# ESP32_backup.net
KiCad netlist of a schematic drawn in Altium Designer
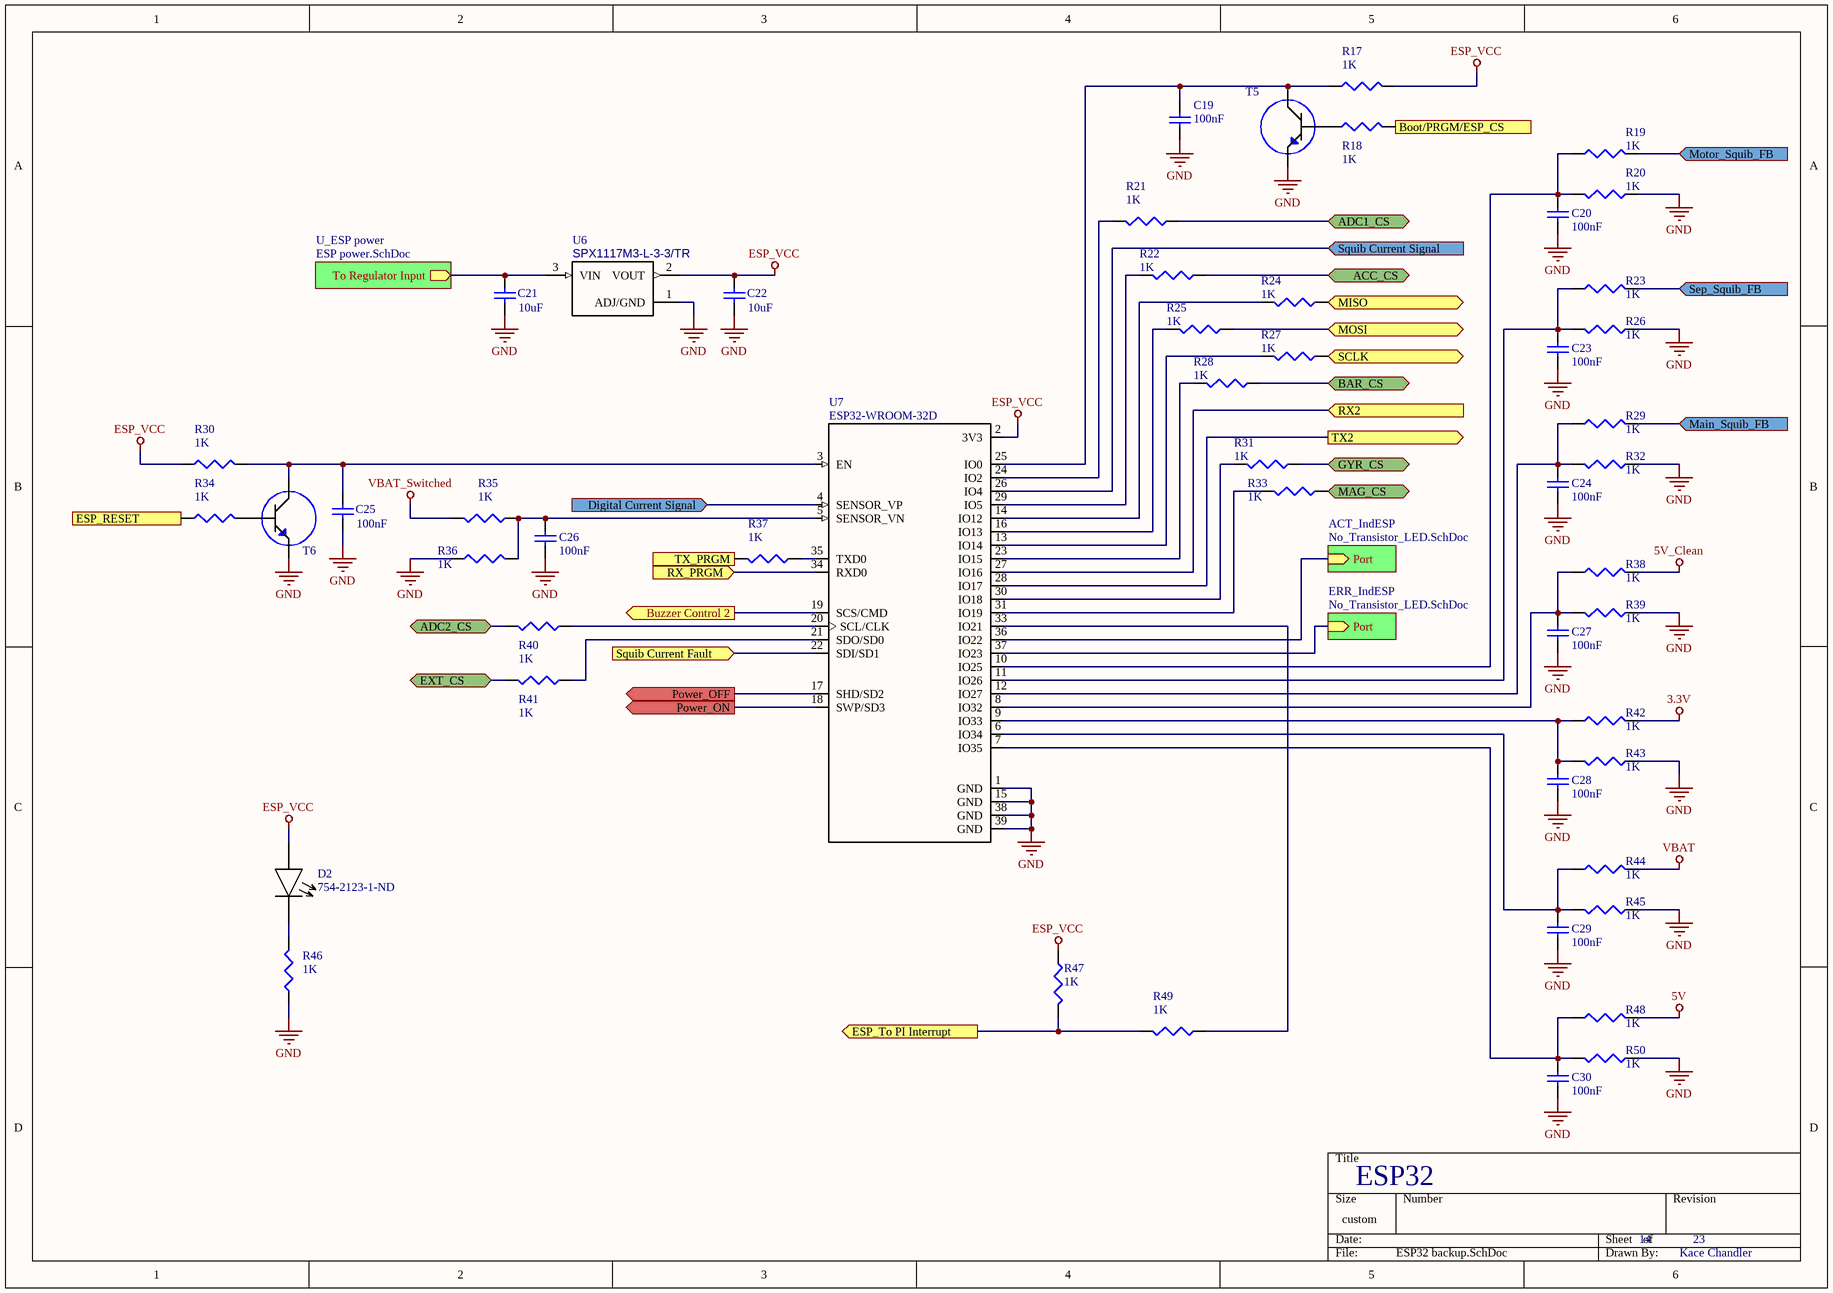
[diagram p0: ESP32 backup.SchDoc]

(export (version "E")
  (design (tool "Eeschema 10.0.6"))
  (components
    (comp (ref "C19")
      (value "100nF")
      (footprint "0805 Footprint")
      (fields (field (name "Comment") "Cap"))
      (libsource (lib "RC0805FR-0751K1L") (part "Cap"))
    )
    (comp (ref "C20")
      (value "100nF")
      (footprint "0603 Footprint")
      (description "Capacitor")
      (fields (field (name "Comment") "Cap") (field (name "PUBLISHER") "Altium Limited"))
      (libsource (lib "Miscellaneous Devices") (part "Cap"))
    )
    (comp (ref "C21")
      (value "10uF")
      (footprint "0805 Footprint")
      (description "Capacitor")
      (fields (field (name "Comment") "Cap") (field (name "PUBLISHER") "Altium Limited"))
      (libsource (lib "Miscellaneous Devices") (part "Cap"))
    )
    (comp (ref "C22")
      (value "10uF")
      (footprint "0805 Footprint")
      (description "Capacitor")
      (fields (field (name "Comment") "Cap") (field (name "PUBLISHER") "Altium Limited"))
      (libsource (lib "Miscellaneous Devices") (part "Cap"))
    )
    (comp (ref "C23")
      (value "100nF")
      (footprint "0603 Footprint")
      (description "Capacitor")
      (fields (field (name "Comment") "Cap") (field (name "PUBLISHER") "Altium Limited"))
      (libsource (lib "Miscellaneous Devices") (part "Cap"))
    )
    (comp (ref "C24")
      (value "100nF")
      (footprint "0603 Footprint")
      (description "Capacitor")
      (fields (field (name "Comment") "Cap") (field (name "PUBLISHER") "Altium Limited"))
      (libsource (lib "Miscellaneous Devices") (part "Cap"))
    )
    (comp (ref "C25")
      (value "100nF")
      (footprint "0805 Footprint")
      (fields (field (name "Comment") "Cap"))
      (libsource (lib "RC0805FR-0751K1L") (part "Cap"))
    )
    (comp (ref "C26")
      (value "100nF")
      (footprint "0603 Footprint")
      (description "Capacitor")
      (fields (field (name "Comment") "Cap") (field (name "PUBLISHER") "Altium Limited"))
      (libsource (lib "Miscellaneous Devices") (part "Cap"))
    )
    (comp (ref "C27")
      (value "100nF")
      (footprint "0603 Footprint")
      (description "Capacitor")
      (fields (field (name "Comment") "Cap") (field (name "PUBLISHER") "Altium Limited"))
      (libsource (lib "Miscellaneous Devices") (part "Cap"))
    )
    (comp (ref "C28")
      (value "100nF")
      (footprint "0603 Footprint")
      (description "Capacitor")
      (fields (field (name "Comment") "Cap") (field (name "PUBLISHER") "Altium Limited"))
      (libsource (lib "Miscellaneous Devices") (part "Cap"))
    )
    (comp (ref "C29")
      (value "100nF")
      (footprint "0603 Footprint")
      (description "Capacitor")
      (fields (field (name "Comment") "Cap") (field (name "PUBLISHER") "Altium Limited"))
      (libsource (lib "Miscellaneous Devices") (part "Cap"))
    )
    (comp (ref "C30")
      (value "100nF")
      (footprint "0603 Footprint")
      (description "Capacitor")
      (fields (field (name "Comment") "Cap") (field (name "PUBLISHER") "Altium Limited"))
      (libsource (lib "Miscellaneous Devices") (part "Cap"))
    )
    (comp (ref "D2")
      (value "LED_R")
      (footprint "0402 footprint")
      (fields (field (name "SUPPLIER PART NUMBER 1") "754-2123-1-ND"))
      (libsource (lib "AvionicsParts") (part "LED_R"))
    )
    (comp (ref "R17")
      (value "1K")
      (description "Resistor")
      (fields (field (name "Comment") "Res3") (field (name "PUBLISHER") "Altium Limited"))
      (libsource (lib "Miscellaneous Devices") (part "Res3"))
    )
    (comp (ref "R18")
      (value "1K")
      (description "Resistor")
      (fields (field (name "Comment") "Res3") (field (name "PUBLISHER") "Altium Limited"))
      (libsource (lib "Miscellaneous Devices") (part "Res3"))
    )
    (comp (ref "R19")
      (value "1K")
      (description "Resistor")
      (fields (field (name "Comment") "Res3") (field (name "PUBLISHER") "Altium Limited"))
      (libsource (lib "Miscellaneous Devices") (part "Res3"))
    )
    (comp (ref "R20")
      (value "1K")
      (description "Resistor")
      (fields (field (name "Comment") "Res3") (field (name "PUBLISHER") "Altium Limited"))
      (libsource (lib "Miscellaneous Devices") (part "Res3"))
    )
    (comp (ref "R21")
      (value "1K")
      (description "Resistor")
      (fields (field (name "Comment") "Res3") (field (name "PUBLISHER") "Altium Limited"))
      (libsource (lib "Miscellaneous Devices") (part "Res3"))
    )
    (comp (ref "R22")
      (value "1K")
      (description "Resistor")
      (fields (field (name "Comment") "Res3") (field (name "PUBLISHER") "Altium Limited"))
      (libsource (lib "Miscellaneous Devices") (part "Res3"))
    )
    (comp (ref "R23")
      (value "1K")
      (description "Resistor")
      (fields (field (name "Comment") "Res3") (field (name "PUBLISHER") "Altium Limited"))
      (libsource (lib "Miscellaneous Devices") (part "Res3"))
    )
    (comp (ref "R24")
      (value "1K")
      (description "Resistor")
      (fields (field (name "Comment") "Res3") (field (name "PUBLISHER") "Altium Limited"))
      (libsource (lib "Miscellaneous Devices") (part "Res3"))
    )
    (comp (ref "R25")
      (value "1K")
      (description "Resistor")
      (fields (field (name "Comment") "Res3") (field (name "PUBLISHER") "Altium Limited"))
      (libsource (lib "Miscellaneous Devices") (part "Res3"))
    )
    (comp (ref "R26")
      (value "1K")
      (description "Resistor")
      (fields (field (name "Comment") "Res3") (field (name "PUBLISHER") "Altium Limited"))
      (libsource (lib "Miscellaneous Devices") (part "Res3"))
    )
    (comp (ref "R27")
      (value "1K")
      (description "Resistor")
      (fields (field (name "Comment") "Res3") (field (name "PUBLISHER") "Altium Limited"))
      (libsource (lib "Miscellaneous Devices") (part "Res3"))
    )
    (comp (ref "R28")
      (value "1K")
      (description "Resistor")
      (fields (field (name "Comment") "Res3") (field (name "PUBLISHER") "Altium Limited"))
      (libsource (lib "Miscellaneous Devices") (part "Res3"))
    )
    (comp (ref "R29")
      (value "1K")
      (description "Resistor")
      (fields (field (name "Comment") "Res3") (field (name "PUBLISHER") "Altium Limited"))
      (libsource (lib "Miscellaneous Devices") (part "Res3"))
    )
    (comp (ref "R30")
      (value "1K")
      (description "Resistor")
      (fields (field (name "Comment") "Res3") (field (name "PUBLISHER") "Altium Limited"))
      (libsource (lib "Miscellaneous Devices") (part "Res3"))
    )
    (comp (ref "R31")
      (value "1K")
      (description "Resistor")
      (fields (field (name "Comment") "Res3") (field (name "PUBLISHER") "Altium Limited"))
      (libsource (lib "Miscellaneous Devices") (part "Res3"))
    )
    (comp (ref "R32")
      (value "1K")
      (description "Resistor")
      (fields (field (name "Comment") "Res3") (field (name "PUBLISHER") "Altium Limited"))
      (libsource (lib "Miscellaneous Devices") (part "Res3"))
    )
    (comp (ref "R33")
      (value "1K")
      (description "Resistor")
      (fields (field (name "Comment") "Res3") (field (name "PUBLISHER") "Altium Limited"))
      (libsource (lib "Miscellaneous Devices") (part "Res3"))
    )
    (comp (ref "R34")
      (value "1K")
      (description "Resistor")
      (fields (field (name "Comment") "Res3") (field (name "PUBLISHER") "Altium Limited"))
      (libsource (lib "Miscellaneous Devices") (part "Res3"))
    )
    (comp (ref "R35")
      (value "1K")
      (description "Resistor")
      (fields (field (name "Comment") "Res3") (field (name "PUBLISHER") "Altium Limited"))
      (libsource (lib "Miscellaneous Devices") (part "Res3"))
    )
    (comp (ref "R36")
      (value "1K")
      (description "Resistor")
      (fields (field (name "Comment") "Res3") (field (name "PUBLISHER") "Altium Limited"))
      (libsource (lib "Miscellaneous Devices") (part "Res3"))
    )
    (comp (ref "R37")
      (value "1K")
      (description "Resistor")
      (fields (field (name "Comment") "Res3") (field (name "PUBLISHER") "Altium Limited"))
      (libsource (lib "Miscellaneous Devices") (part "Res3"))
    )
    (comp (ref "R38")
      (value "1K")
      (description "Resistor")
      (fields (field (name "Comment") "Res3") (field (name "PUBLISHER") "Altium Limited"))
      (libsource (lib "Miscellaneous Devices") (part "Res3"))
    )
    (comp (ref "R39")
      (value "1K")
      (description "Resistor")
      (fields (field (name "Comment") "Res3") (field (name "PUBLISHER") "Altium Limited"))
      (libsource (lib "Miscellaneous Devices") (part "Res3"))
    )
    (comp (ref "R40")
      (value "1K")
      (description "Resistor")
      (fields (field (name "Comment") "Res3") (field (name "PUBLISHER") "Altium Limited"))
      (libsource (lib "Miscellaneous Devices") (part "Res3"))
    )
    (comp (ref "R41")
      (value "1K")
      (description "Resistor")
      (fields (field (name "Comment") "Res3") (field (name "PUBLISHER") "Altium Limited"))
      (libsource (lib "Miscellaneous Devices") (part "Res3"))
    )
    (comp (ref "R42")
      (value "1K")
      (description "Resistor")
      (fields (field (name "Comment") "Res3") (field (name "PUBLISHER") "Altium Limited"))
      (libsource (lib "Miscellaneous Devices") (part "Res3"))
    )
    (comp (ref "R43")
      (value "1K")
      (description "Resistor")
      (fields (field (name "Comment") "Res3") (field (name "PUBLISHER") "Altium Limited"))
      (libsource (lib "Miscellaneous Devices") (part "Res3"))
    )
    (comp (ref "R44")
      (value "1K")
      (description "Resistor")
      (fields (field (name "Comment") "Res3") (field (name "PUBLISHER") "Altium Limited"))
      (libsource (lib "Miscellaneous Devices") (part "Res3"))
    )
    (comp (ref "R45")
      (value "1K")
      (description "Resistor")
      (fields (field (name "Comment") "Res3") (field (name "PUBLISHER") "Altium Limited"))
      (libsource (lib "Miscellaneous Devices") (part "Res3"))
    )
    (comp (ref "R46")
      (value "1K")
      (description "Resistor")
      (fields (field (name "Comment") "Res3") (field (name "PUBLISHER") "Altium Limited"))
      (libsource (lib "Miscellaneous Devices") (part "Res3"))
    )
    (comp (ref "R47")
      (value "1K")
      (footprint "J1-0603")
      (description "Resistor")
      (fields (field (name "Comment") "Res3") (field (name "PUBLISHER") "Altium Limited"))
      (libsource (lib "Miscellaneous Devices") (part "Res3"))
    )
    (comp (ref "R48")
      (value "1K")
      (description "Resistor")
      (fields (field (name "Comment") "Res3") (field (name "PUBLISHER") "Altium Limited"))
      (libsource (lib "Miscellaneous Devices") (part "Res3"))
    )
    (comp (ref "R49")
      (value "1K")
      (description "Resistor")
      (fields (field (name "Comment") "Res3") (field (name "PUBLISHER") "Altium Limited"))
      (libsource (lib "Miscellaneous Devices") (part "Res3"))
    )
    (comp (ref "R50")
      (value "1K")
      (description "Resistor")
      (fields (field (name "Comment") "Res3") (field (name "PUBLISHER") "Altium Limited"))
      (libsource (lib "Miscellaneous Devices") (part "Res3"))
    )
    (comp (ref "T5")
      (value "MMBT2222ALT1")
      (footprint "BJT")
      (description "Trans NPN 40V 0.6A SOT23")
      (fields (field (name "MF") "ON Semiconductor"))
      (libsource (lib "AvionicsParts") (part "BJT NPN"))
    )
    (comp (ref "T6")
      (value "MMBT2222ALT1")
      (footprint "BJT")
      (description "Trans NPN 40V 0.6A SOT23")
      (fields (field (name "MF") "ON Semiconductor"))
      (libsource (lib "AvionicsParts") (part "BJT NPN"))
    )
    (comp (ref "U6")
      (value "3.3V Regulator")
      (footprint "*DPAK229P990X238-4N")
      (description "NCP1117DT33T5GOSCT-ND 3.3V linear regulator")
      (fields (field (name "MF") "MaxLinear, Inc.") (field (name "MP") "SPX1117M3-L-3-3/TR"))
      (libsource (lib "AvionicsParts") (part "3-3VReg"))
    )
    (comp (ref "U7")
      (value "ESP32-WROOM-32D")
      (footprint "*MODULE_ESP32-WROOM-32D")
      (description "IC: SoC; GPIO, I2C, I2S, IR, SD, SDIO, SPI, UART; 2.7Ã·3.6VDC; 20dBm")
      (fields (field (name "MF") "Espressif Systems"))
      (libsource (lib "AvionicsParts") (part "ESP32-WROOM-32D"))
    )
  )
  (nets
    (net (code "1") (name "/ACC_CS") (class "Default")
      (node (ref "R22") (pin "1") (pinfunction "1_1") (pintype "passive"))
    )
    (net (code "2") (name "/ADC1_CS") (class "Default")
      (node (ref "R21") (pin "1") (pinfunction "1_1") (pintype "passive"))
    )
    (net (code "3") (name "/ADC2_CS") (class "Default")
      (node (ref "R40") (pin "2") (pinfunction "2_2") (pintype "passive"))
    )
    (net (code "4") (name "/BAR_CS") (class "Default")
      (node (ref "R28") (pin "1") (pinfunction "1_1") (pintype "passive"))
    )
    (net (code "5") (name "/Boot{slash}PRGM{slash}ESP_CS") (class "Default")
      (node (ref "R18") (pin "2") (pinfunction "2_2") (pintype "passive"))
    )
    (net (code "6") (name "/Buzzer Control 2") (class "Default")
      (node (ref "U7") (pin "19") (pinfunction "SCS/CMD_19") (pintype "bidirectional"))
    )
    (net (code "7") (name "/Digital Current Signal") (class "Default")
      (node (ref "U7") (pin "4") (pinfunction "SENSOR_VP_4") (pintype "input"))
    )
    (net (code "8") (name "/ESP_RESET") (class "Default")
      (node (ref "R34") (pin "1") (pinfunction "1_1") (pintype "passive"))
    )
    (net (code "9") (name "/ESP_To PI Interrupt") (class "Default")
      (node (ref "R47") (pin "2") (pinfunction "2_2") (pintype "passive"))
      (node (ref "R49") (pin "2") (pinfunction "2_2") (pintype "passive"))
    )
    (net (code "10") (name "/EXT_CS") (class "Default")
      (node (ref "R41") (pin "2") (pinfunction "2_2") (pintype "passive"))
    )
    (net (code "11") (name "/GYR_CS") (class "Default")
      (node (ref "R31") (pin "1") (pinfunction "1_1") (pintype "passive"))
    )
    (net (code "12") (name "/MAG_CS") (class "Default")
      (node (ref "R33") (pin "1") (pinfunction "1_1") (pintype "passive"))
    )
    (net (code "13") (name "/MISO") (class "Default")
      (node (ref "R24") (pin "1") (pinfunction "1_1") (pintype "passive"))
    )
    (net (code "14") (name "/MOSI") (class "Default")
      (node (ref "R25") (pin "1") (pinfunction "1_1") (pintype "passive"))
    )
    (net (code "15") (name "/Main_Squib_FB") (class "Default")
      (node (ref "R29") (pin "2") (pinfunction "2_2") (pintype "passive"))
    )
    (net (code "16") (name "/Motor_Squib_FB") (class "Default")
      (node (ref "R19") (pin "2") (pinfunction "2_2") (pintype "passive"))
    )
    (net (code "17") (name "/Port") (class "Default")
      (node (ref "U7") (pin "37") (pinfunction "IO23_37") (pintype "bidirectional"))
    )
    (net (code "18") (name "/Port_1") (class "Default")
      (node (ref "U7") (pin "36") (pinfunction "IO22_36") (pintype "bidirectional"))
    )
    (net (code "19") (name "/Power_OFF") (class "Default")
      (node (ref "U7") (pin "17") (pinfunction "SHD/SD2_17") (pintype "bidirectional"))
    )
    (net (code "20") (name "/Power_ON") (class "Default")
      (node (ref "U7") (pin "18") (pinfunction "SWP/SD3_18") (pintype "bidirectional"))
    )
    (net (code "21") (name "/RX2") (class "Default")
      (node (ref "U7") (pin "27") (pinfunction "IO16_27") (pintype "bidirectional"))
    )
    (net (code "22") (name "/RX_PRGM") (class "Default")
      (node (ref "U7") (pin "34") (pinfunction "RXD0_34") (pintype "bidirectional"))
    )
    (net (code "23") (name "/SCLK") (class "Default")
      (node (ref "R27") (pin "1") (pinfunction "1_1") (pintype "passive"))
    )
    (net (code "24") (name "/Sep_Squib_FB") (class "Default")
      (node (ref "R23") (pin "2") (pinfunction "2_2") (pintype "passive"))
    )
    (net (code "25") (name "/Squib Current Fault") (class "Default")
      (node (ref "U7") (pin "22") (pinfunction "SDI/SD1_22") (pintype "bidirectional"))
    )
    (net (code "26") (name "/Squib Current Signal") (class "Default")
      (node (ref "U7") (pin "26") (pinfunction "IO4_26") (pintype "bidirectional"))
    )
    (net (code "27") (name "/TX2") (class "Default")
      (node (ref "U7") (pin "28") (pinfunction "IO17_28") (pintype "bidirectional"))
    )
    (net (code "28") (name "/TX_PRGM") (class "Default")
      (node (ref "R37") (pin "2") (pinfunction "2_2") (pintype "passive"))
    )
    (net (code "29") (name "/To Regulator Input") (class "Default")
      (node (ref "C21") (pin "2") (pinfunction "2_2") (pintype "passive"))
      (node (ref "U6") (pin "3") (pinfunction "VIN_3") (pintype "input"))
    )
    (net (code "30") (name "3.3V") (class "Default")
      (node (ref "R42") (pin "2") (pinfunction "2_2") (pintype "passive"))
    )
    (net (code "31") (name "5V") (class "Default")
      (node (ref "R48") (pin "2") (pinfunction "2_2") (pintype "passive"))
    )
    (net (code "32") (name "5V_Clean") (class "Default")
      (node (ref "R38") (pin "2") (pinfunction "2_2") (pintype "passive"))
    )
    (net (code "33") (name "ESP_VCC") (class "Default")
      (node (ref "C22") (pin "2") (pinfunction "2_2") (pintype "passive"))
      (node (ref "D2") (pin "1") (pinfunction "1_1") (pintype "passive"))
      (node (ref "R17") (pin "1") (pinfunction "1_1") (pintype "passive"))
      (node (ref "R30") (pin "1") (pinfunction "1_1") (pintype "passive"))
      (node (ref "R47") (pin "1") (pinfunction "1_1") (pintype "passive"))
      (node (ref "U6") (pin "2") (pinfunction "VOUT_2") (pintype "output"))
      (node (ref "U7") (pin "2") (pinfunction "3V3_2") (pintype "power_in"))
    )
    (net (code "34") (name "GND") (class "Default")
      (node (ref "C19") (pin "1") (pinfunction "1_1") (pintype "passive"))
      (node (ref "C20") (pin "1") (pinfunction "1_1") (pintype "passive"))
      (node (ref "C21") (pin "1") (pinfunction "1_1") (pintype "passive"))
      (node (ref "C22") (pin "1") (pinfunction "1_1") (pintype "passive"))
      (node (ref "C23") (pin "1") (pinfunction "1_1") (pintype "passive"))
      (node (ref "C24") (pin "1") (pinfunction "1_1") (pintype "passive"))
      (node (ref "C25") (pin "1") (pinfunction "1_1") (pintype "passive"))
      (node (ref "C26") (pin "1") (pinfunction "1_1") (pintype "passive"))
      (node (ref "C27") (pin "1") (pinfunction "1_1") (pintype "passive"))
      (node (ref "C28") (pin "1") (pinfunction "1_1") (pintype "passive"))
      (node (ref "C29") (pin "1") (pinfunction "1_1") (pintype "passive"))
      (node (ref "C30") (pin "1") (pinfunction "1_1") (pintype "passive"))
      (node (ref "R20") (pin "1") (pinfunction "1_1") (pintype "passive"))
      (node (ref "R26") (pin "1") (pinfunction "1_1") (pintype "passive"))
      (node (ref "R32") (pin "1") (pinfunction "1_1") (pintype "passive"))
      (node (ref "R36") (pin "1") (pinfunction "1_1") (pintype "passive"))
      (node (ref "R39") (pin "1") (pinfunction "1_1") (pintype "passive"))
      (node (ref "R43") (pin "1") (pinfunction "1_1") (pintype "passive"))
      (node (ref "R45") (pin "1") (pinfunction "1_1") (pintype "passive"))
      (node (ref "R46") (pin "1") (pinfunction "1_1") (pintype "passive"))
      (node (ref "R50") (pin "1") (pinfunction "1_1") (pintype "passive"))
      (node (ref "T5") (pin "2") (pinfunction "E_2") (pintype "passive"))
      (node (ref "T6") (pin "2") (pinfunction "E_2") (pintype "passive"))
      (node (ref "U6") (pin "1") (pinfunction "ADJ/GND_1") (pintype "power_in"))
      (node (ref "U7") (pin "1") (pinfunction "GND_1") (pintype "power_in"))
      (node (ref "U7") (pin "15") (pinfunction "GND_15") (pintype "power_in"))
      (node (ref "U7") (pin "38") (pinfunction "GND_38") (pintype "power_in"))
      (node (ref "U7") (pin "39") (pinfunction "GND_39") (pintype "power_in"))
    )
    (net (code "35") (name "Net-(D2-Pad2)") (class "Default")
      (node (ref "D2") (pin "2") (pinfunction "2_2") (pintype "passive"))
      (node (ref "R46") (pin "2") (pinfunction "2_2") (pintype "passive"))
    )
    (net (code "36") (name "Net-(T5-B)") (class "Default")
      (node (ref "R18") (pin "1") (pinfunction "1_1") (pintype "passive"))
      (node (ref "T5") (pin "1") (pinfunction "B_1") (pintype "passive"))
    )
    (net (code "37") (name "Net-(T5-C)") (class "Default")
      (node (ref "C19") (pin "2") (pinfunction "2_2") (pintype "passive"))
      (node (ref "R17") (pin "2") (pinfunction "2_2") (pintype "passive"))
      (node (ref "T5") (pin "3") (pinfunction "C_3") (pintype "passive"))
      (node (ref "U7") (pin "25") (pinfunction "IO0_25") (pintype "bidirectional"))
    )
    (net (code "38") (name "Net-(T6-B)") (class "Default")
      (node (ref "R34") (pin "2") (pinfunction "2_2") (pintype "passive"))
      (node (ref "T6") (pin "1") (pinfunction "B_1") (pintype "passive"))
    )
    (net (code "39") (name "Net-(T6-C)") (class "Default")
      (node (ref "C25") (pin "2") (pinfunction "2_2") (pintype "passive"))
      (node (ref "R30") (pin "2") (pinfunction "2_2") (pintype "passive"))
      (node (ref "T6") (pin "3") (pinfunction "C_3") (pintype "passive"))
      (node (ref "U7") (pin "3") (pinfunction "EN_3") (pintype "input"))
    )
    (net (code "40") (name "Net-(U7-IO2)") (class "Default")
      (node (ref "R21") (pin "2") (pinfunction "2_2") (pintype "passive"))
      (node (ref "U7") (pin "24") (pinfunction "IO2_24") (pintype "bidirectional"))
    )
    (net (code "41") (name "Net-(U7-IO5)") (class "Default")
      (node (ref "R22") (pin "2") (pinfunction "2_2") (pintype "passive"))
      (node (ref "U7") (pin "29") (pinfunction "IO5_29") (pintype "bidirectional"))
    )
    (net (code "42") (name "Net-(U7-IO12)") (class "Default")
      (node (ref "R24") (pin "2") (pinfunction "2_2") (pintype "passive"))
      (node (ref "U7") (pin "14") (pinfunction "IO12_14") (pintype "bidirectional"))
    )
    (net (code "43") (name "Net-(U7-IO13)") (class "Default")
      (node (ref "R25") (pin "2") (pinfunction "2_2") (pintype "passive"))
      (node (ref "U7") (pin "16") (pinfunction "IO13_16") (pintype "bidirectional"))
    )
    (net (code "44") (name "Net-(U7-IO14)") (class "Default")
      (node (ref "R27") (pin "2") (pinfunction "2_2") (pintype "passive"))
      (node (ref "U7") (pin "13") (pinfunction "IO14_13") (pintype "bidirectional"))
    )
    (net (code "45") (name "Net-(U7-IO15)") (class "Default")
      (node (ref "R28") (pin "2") (pinfunction "2_2") (pintype "passive"))
      (node (ref "U7") (pin "23") (pinfunction "IO15_23") (pintype "bidirectional"))
    )
    (net (code "46") (name "Net-(U7-IO18)") (class "Default")
      (node (ref "R31") (pin "2") (pinfunction "2_2") (pintype "passive"))
      (node (ref "U7") (pin "30") (pinfunction "IO18_30") (pintype "bidirectional"))
    )
    (net (code "47") (name "Net-(U7-IO19)") (class "Default")
      (node (ref "R33") (pin "2") (pinfunction "2_2") (pintype "passive"))
      (node (ref "U7") (pin "31") (pinfunction "IO19_31") (pintype "bidirectional"))
    )
    (net (code "48") (name "Net-(U7-IO21)") (class "Default")
      (node (ref "R49") (pin "1") (pinfunction "1_1") (pintype "passive"))
      (node (ref "U7") (pin "33") (pinfunction "IO21_33") (pintype "bidirectional"))
    )
    (net (code "49") (name "Net-(U7-IO25)") (class "Default")
      (node (ref "C20") (pin "2") (pinfunction "2_2") (pintype "passive"))
      (node (ref "R19") (pin "1") (pinfunction "1_1") (pintype "passive"))
      (node (ref "R20") (pin "2") (pinfunction "2_2") (pintype "passive"))
      (node (ref "U7") (pin "10") (pinfunction "IO25_10") (pintype "bidirectional"))
    )
    (net (code "50") (name "Net-(U7-IO26)") (class "Default")
      (node (ref "C23") (pin "2") (pinfunction "2_2") (pintype "passive"))
      (node (ref "R23") (pin "1") (pinfunction "1_1") (pintype "passive"))
      (node (ref "R26") (pin "2") (pinfunction "2_2") (pintype "passive"))
      (node (ref "U7") (pin "11") (pinfunction "IO26_11") (pintype "bidirectional"))
    )
    (net (code "51") (name "Net-(U7-IO27)") (class "Default")
      (node (ref "C24") (pin "2") (pinfunction "2_2") (pintype "passive"))
      (node (ref "R29") (pin "1") (pinfunction "1_1") (pintype "passive"))
      (node (ref "R32") (pin "2") (pinfunction "2_2") (pintype "passive"))
      (node (ref "U7") (pin "12") (pinfunction "IO27_12") (pintype "bidirectional"))
    )
    (net (code "52") (name "Net-(U7-IO32)") (class "Default")
      (node (ref "C27") (pin "2") (pinfunction "2_2") (pintype "passive"))
      (node (ref "R38") (pin "1") (pinfunction "1_1") (pintype "passive"))
      (node (ref "R39") (pin "2") (pinfunction "2_2") (pintype "passive"))
      (node (ref "U7") (pin "8") (pinfunction "IO32_8") (pintype "bidirectional"))
    )
    (net (code "53") (name "Net-(U7-IO33)") (class "Default")
      (node (ref "C28") (pin "2") (pinfunction "2_2") (pintype "passive"))
      (node (ref "R42") (pin "1") (pinfunction "1_1") (pintype "passive"))
      (node (ref "R43") (pin "2") (pinfunction "2_2") (pintype "passive"))
      (node (ref "U7") (pin "9") (pinfunction "IO33_9") (pintype "bidirectional"))
    )
    (net (code "54") (name "Net-(U7-IO34)") (class "Default")
      (node (ref "C29") (pin "2") (pinfunction "2_2") (pintype "passive"))
      (node (ref "R44") (pin "1") (pinfunction "1_1") (pintype "passive"))
      (node (ref "R45") (pin "2") (pinfunction "2_2") (pintype "passive"))
      (node (ref "U7") (pin "6") (pinfunction "IO34_6") (pintype "bidirectional"))
    )
    (net (code "55") (name "Net-(U7-IO35)") (class "Default")
      (node (ref "C30") (pin "2") (pinfunction "2_2") (pintype "passive"))
      (node (ref "R48") (pin "1") (pinfunction "1_1") (pintype "passive"))
      (node (ref "R50") (pin "2") (pinfunction "2_2") (pintype "passive"))
      (node (ref "U7") (pin "7") (pinfunction "IO35_7") (pintype "bidirectional"))
    )
    (net (code "56") (name "Net-(U7-SCL{slash}CLK)") (class "Default")
      (node (ref "R40") (pin "1") (pinfunction "1_1") (pintype "passive"))
      (node (ref "U7") (pin "20") (pinfunction "SCL/CLK_20") (pintype "bidirectional"))
    )
    (net (code "57") (name "Net-(U7-SDO{slash}SD0)") (class "Default")
      (node (ref "R41") (pin "1") (pinfunction "1_1") (pintype "passive"))
      (node (ref "U7") (pin "21") (pinfunction "SDO/SD0_21") (pintype "bidirectional"))
    )
    (net (code "58") (name "Net-(U7-SENSOR_VN)") (class "Default")
      (node (ref "C26") (pin "2") (pinfunction "2_2") (pintype "passive"))
      (node (ref "R35") (pin "1") (pinfunction "1_1") (pintype "passive"))
      (node (ref "R36") (pin "2") (pinfunction "2_2") (pintype "passive"))
      (node (ref "U7") (pin "5") (pinfunction "SENSOR_VN_5") (pintype "input"))
    )
    (net (code "59") (name "Net-(U7-TXD0)") (class "Default")
      (node (ref "R37") (pin "1") (pinfunction "1_1") (pintype "passive"))
      (node (ref "U7") (pin "35") (pinfunction "TXD0_35") (pintype "bidirectional"))
    )
    (net (code "60") (name "VBAT") (class "Default")
      (node (ref "R44") (pin "2") (pinfunction "2_2") (pintype "passive"))
    )
    (net (code "61") (name "VBAT_Switched") (class "Default")
      (node (ref "R35") (pin "2") (pinfunction "2_2") (pintype "passive"))
    )
  )
)
